# SCH_My-USB-Hub_2024-06-27.net
KiCad netlist of a schematic drawn in EasyEDA
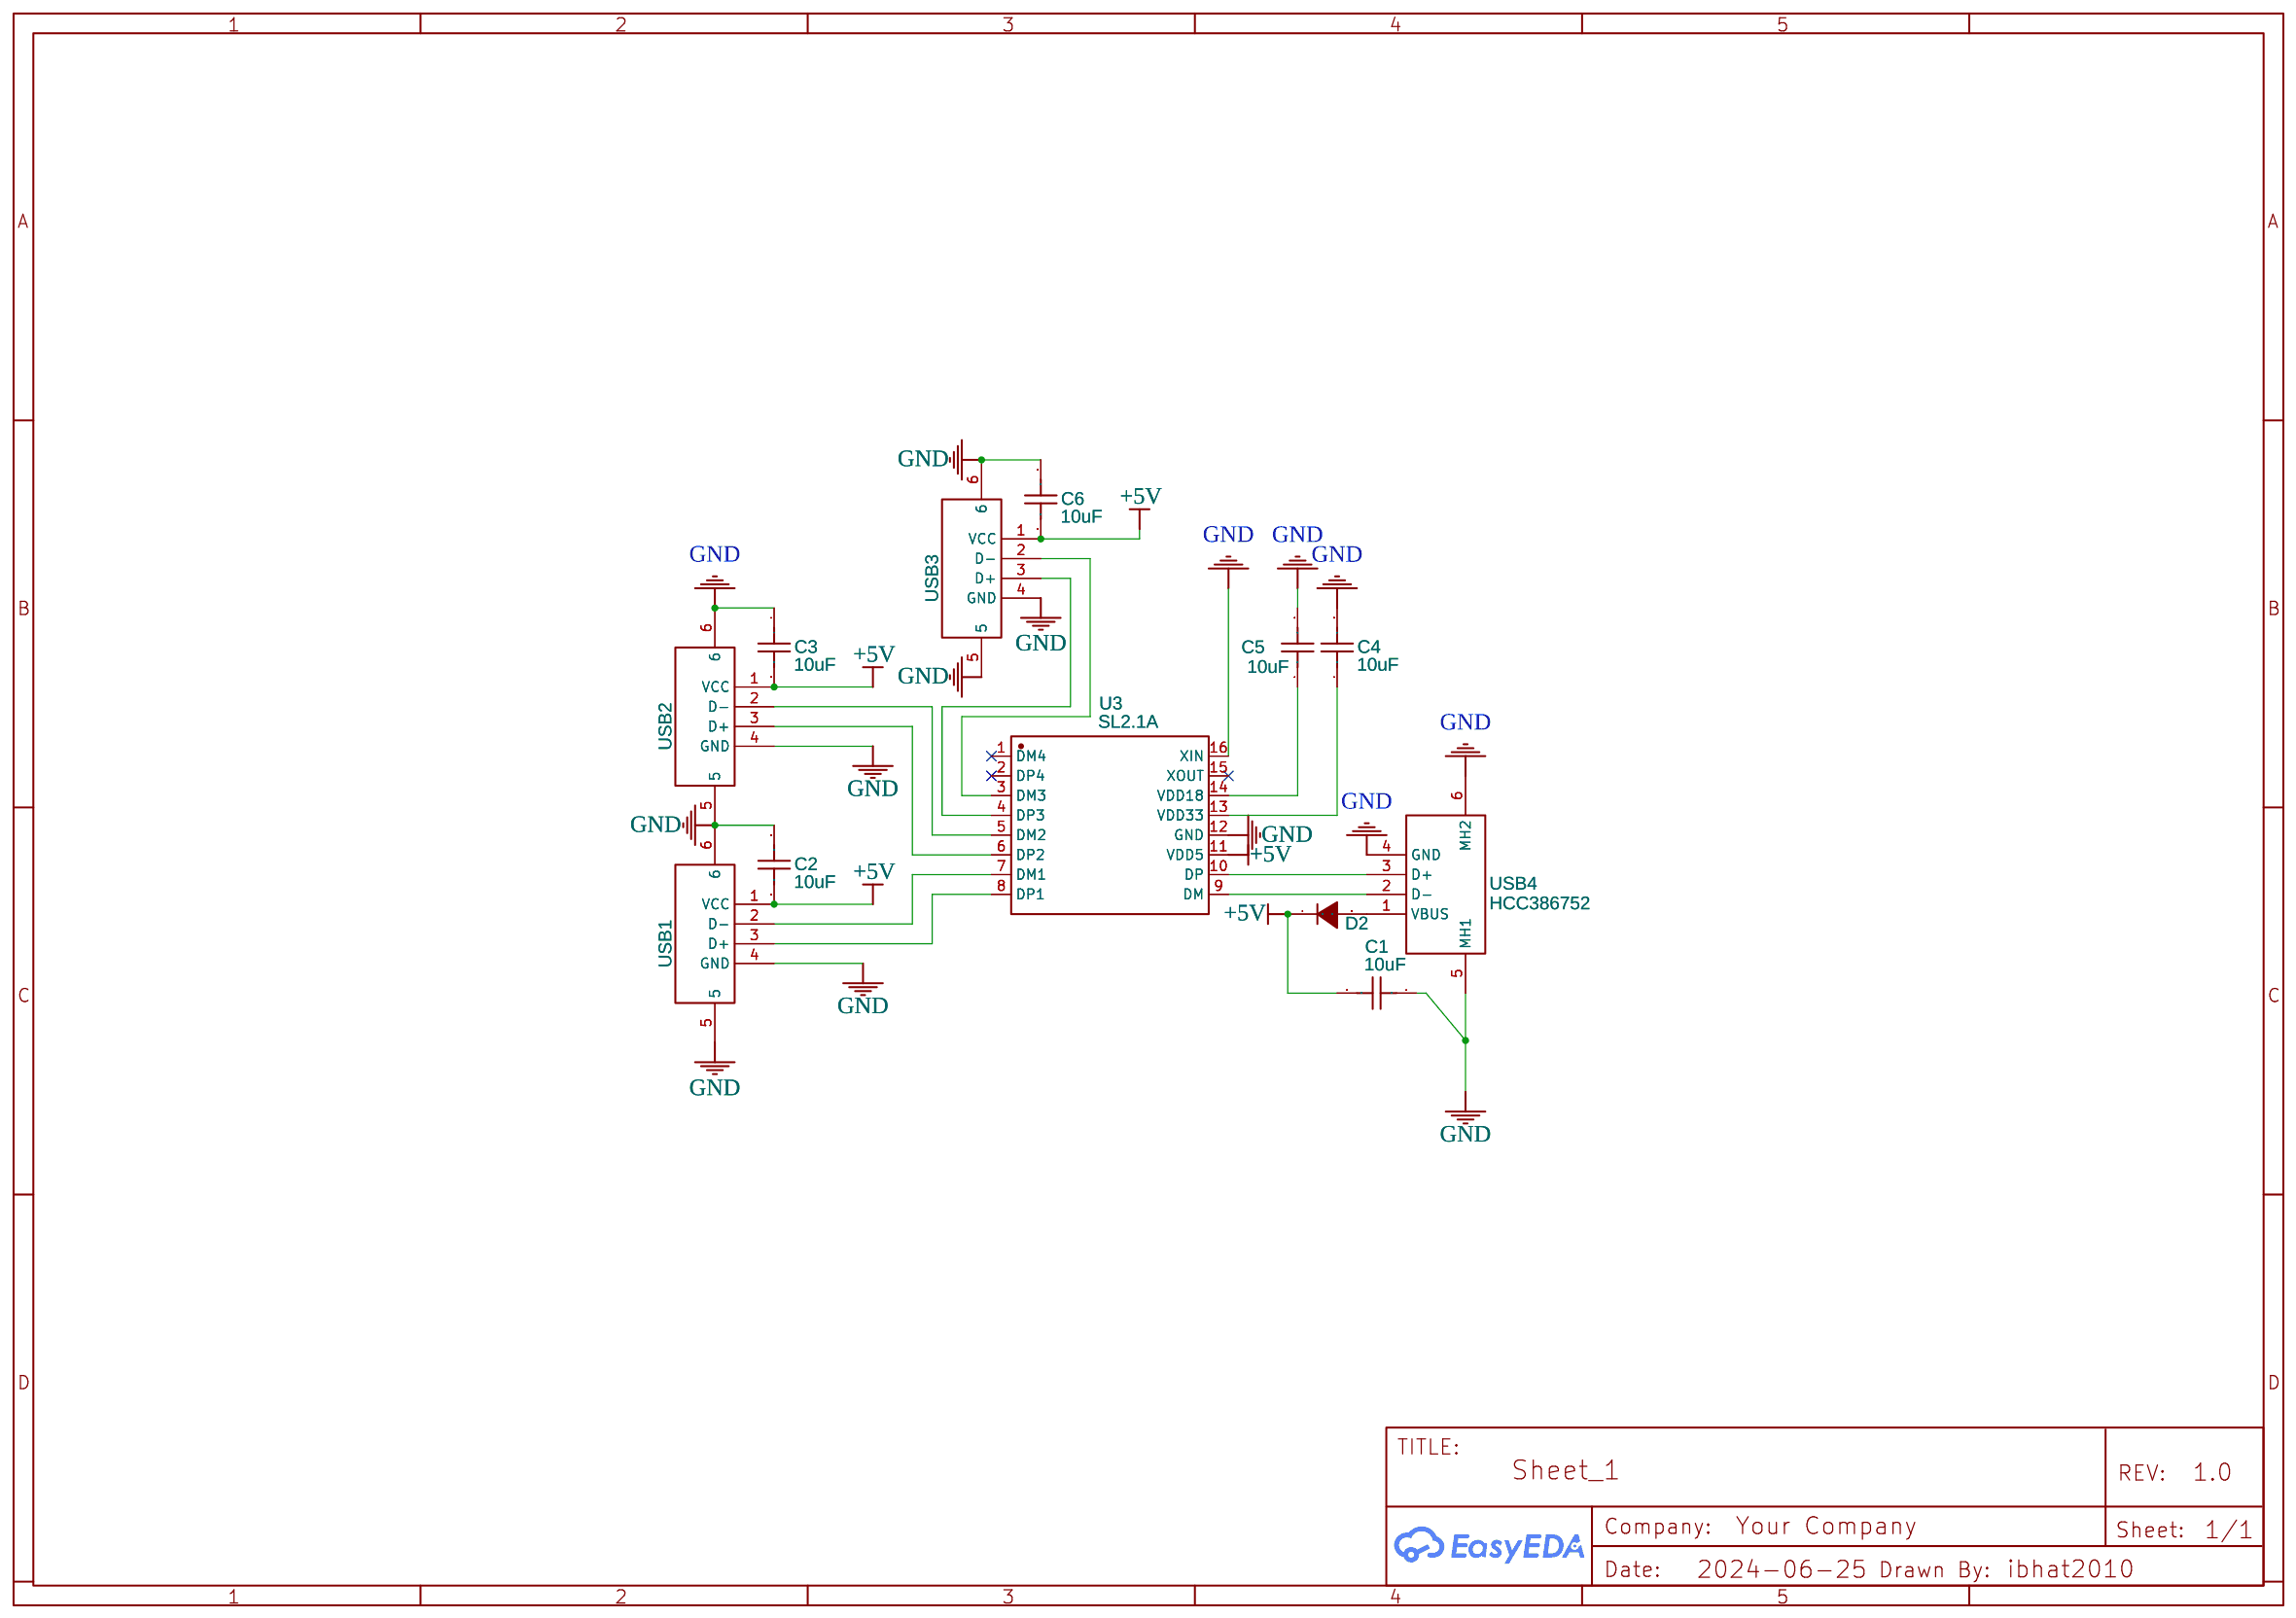
[diagram p0: schematic sheet]

(export (version "E")
  (design (tool "Eeschema 10.0.6"))
  (components
    (comp (ref "C1")
      (value "10uF")
      (fields
        (field (name "Manufacturer Part") "CL10A106KP8NNNC")
        (field (name "Manufacturer") "SAMSUNG(三星)")
      )
      (libsource (lib "") (part "CL10A106KP8NNNC_1"))
    )
    (comp (ref "C2")
      (value "10uF")
      (fields
        (field (name "Manufacturer Part") "CL10A106KP8NNNC")
        (field (name "Manufacturer") "SAMSUNG(三星)")
      )
      (libsource (lib "") (part "CL10A106KP8NNNC"))
    )
    (comp (ref "C3")
      (value "10uF")
      (fields
        (field (name "Manufacturer Part") "CL10A106KP8NNNC")
        (field (name "Manufacturer") "SAMSUNG(三星)")
      )
      (libsource (lib "") (part "CL10A106KP8NNNC"))
    )
    (comp (ref "C4") (value "10uF") (libsource (lib "") (part "C_0603_US")))
    (comp (ref "C5") (value "10uF") (libsource (lib "") (part "C_0603_US")))
    (comp (ref "C6")
      (value "10uF")
      (fields
        (field (name "Manufacturer Part") "CL10A106KP8NNNC")
        (field (name "Manufacturer") "SAMSUNG(三星)")
      )
      (libsource (lib "") (part "CL10A106KP8NNNC"))
    )
    (comp (ref "D2")
      (value "NSR0320MW2T1G")
      (fields (field (name "Manufacturer") "onsemi(安森美)"))
      (libsource (lib "") (part "NSR0320MW2T1G"))
    )
    (comp (ref "U3")
      (value "SL2.1A")
      (fields (field (name "Manufacturer") "CoreChips(和芯润德)"))
      (libsource (lib "") (part "SL2.1A"))
    )
    (comp (ref "USB1")
      (value "USB-AF-90-14.4X13.6-H7.0-DIP")
      (fields (field (name "Manufacturer Part") "903-131A1011D10100") (field (name "Manufacturer") "精拓金"))
      (libsource (lib "") (part "USB-AF-90-14.4X13.6-H7.0-DIP"))
    )
    (comp (ref "USB2")
      (value "USB-AF-90-14.4X13.6-H7.0-DIP")
      (fields (field (name "Manufacturer Part") "903-131A1011D10100") (field (name "Manufacturer") "精拓金"))
      (libsource (lib "") (part "USB-AF-90-14.4X13.6-H7.0-DIP"))
    )
    (comp (ref "USB3")
      (value "USB-AF-90-14.4X13.6-H7.0-DIP")
      (fields (field (name "Manufacturer Part") "903-131A1011D10100") (field (name "Manufacturer") "精拓金"))
      (libsource (lib "") (part "USB-AF-90-14.4X13.6-H7.0-DIP"))
    )
    (comp (ref "USB4")
      (value "HCC386752")
      (fields (field (name "Manufacturer Part") "U-USBAR04P-M003") (field (name "Manufacturer") "Ckmtw(灿科盟)"))
      (libsource (lib "") (part "HCC386752"))
    )
  )
  (nets
    (net (code "1") (name "+5V") (class "Default")
      (node (ref "C1") (pin "2") (pinfunction "2_2") (pintype "unspecified"))
      (node (ref "C2") (pin "2") (pinfunction "2_2") (pintype "unspecified"))
      (node (ref "C3") (pin "2") (pinfunction "2_2") (pintype "unspecified"))
      (node (ref "C6") (pin "2") (pinfunction "2_2") (pintype "unspecified"))
      (node (ref "D2") (pin "1") (pinfunction "C_1") (pintype "unspecified"))
      (node (ref "U3") (pin "11") (pinfunction "VDD5_11") (pintype "unspecified"))
      (node (ref "USB1") (pin "1") (pinfunction "VCC_1") (pintype "unspecified"))
      (node (ref "USB2") (pin "1") (pinfunction "VCC_1") (pintype "unspecified"))
      (node (ref "USB3") (pin "1") (pinfunction "VCC_1") (pintype "unspecified"))
    )
    (net (code "2") (name "GND") (class "Default")
      (node (ref "C1") (pin "1") (pinfunction "1_1") (pintype "unspecified"))
      (node (ref "C2") (pin "1") (pinfunction "1_1") (pintype "unspecified"))
      (node (ref "C3") (pin "1") (pinfunction "1_1") (pintype "unspecified"))
      (node (ref "C4") (pin "2") (pinfunction "2_2") (pintype "unspecified"))
      (node (ref "C5") (pin "2") (pinfunction "2_2") (pintype "unspecified"))
      (node (ref "C6") (pin "1") (pinfunction "1_1") (pintype "unspecified"))
      (node (ref "U3") (pin "12") (pinfunction "GND_12") (pintype "unspecified"))
      (node (ref "U3") (pin "16") (pinfunction "XIN_16") (pintype "unspecified"))
      (node (ref "USB1") (pin "4") (pinfunction "GND_4") (pintype "unspecified"))
      (node (ref "USB1") (pin "5") (pinfunction "5_5") (pintype "unspecified"))
      (node (ref "USB1") (pin "6") (pinfunction "6_6") (pintype "unspecified"))
      (node (ref "USB2") (pin "4") (pinfunction "GND_4") (pintype "unspecified"))
      (node (ref "USB2") (pin "5") (pinfunction "5_5") (pintype "unspecified"))
      (node (ref "USB2") (pin "6") (pinfunction "6_6") (pintype "unspecified"))
      (node (ref "USB3") (pin "4") (pinfunction "GND_4") (pintype "unspecified"))
      (node (ref "USB3") (pin "5") (pinfunction "5_5") (pintype "unspecified"))
      (node (ref "USB3") (pin "6") (pinfunction "6_6") (pintype "unspecified"))
      (node (ref "USB4") (pin "4") (pinfunction "GND_4") (pintype "unspecified"))
      (node (ref "USB4") (pin "5") (pinfunction "MH1_5") (pintype "unspecified"))
      (node (ref "USB4") (pin "6") (pinfunction "MH2_6") (pintype "unspecified"))
    )
    (net (code "3") (name "Net-(D2-A)") (class "Default")
      (node (ref "D2") (pin "2") (pinfunction "A_2") (pintype "unspecified"))
      (node (ref "USB4") (pin "1") (pinfunction "VBUS_1") (pintype "unspecified"))
    )
    (net (code "4") (name "Net-(U3-DM)") (class "Default")
      (node (ref "U3") (pin "9") (pinfunction "DM_9") (pintype "unspecified"))
      (node (ref "USB4") (pin "2") (pinfunction "D-_2") (pintype "unspecified"))
    )
    (net (code "5") (name "Net-(U3-DM1)") (class "Default")
      (node (ref "U3") (pin "7") (pinfunction "DM1_7") (pintype "unspecified"))
      (node (ref "USB1") (pin "2") (pinfunction "D-_2") (pintype "unspecified"))
    )
    (net (code "6") (name "Net-(U3-DM2)") (class "Default")
      (node (ref "U3") (pin "5") (pinfunction "DM2_5") (pintype "unspecified"))
      (node (ref "USB2") (pin "2") (pinfunction "D-_2") (pintype "unspecified"))
    )
    (net (code "7") (name "Net-(U3-DM3)") (class "Default")
      (node (ref "U3") (pin "3") (pinfunction "DM3_3") (pintype "unspecified"))
      (node (ref "USB3") (pin "2") (pinfunction "D-_2") (pintype "unspecified"))
    )
    (net (code "8") (name "Net-(U3-DP)") (class "Default")
      (node (ref "U3") (pin "10") (pinfunction "DP_10") (pintype "unspecified"))
      (node (ref "USB4") (pin "3") (pinfunction "D+_3") (pintype "unspecified"))
    )
    (net (code "9") (name "Net-(U3-DP1)") (class "Default")
      (node (ref "U3") (pin "8") (pinfunction "DP1_8") (pintype "unspecified"))
      (node (ref "USB1") (pin "3") (pinfunction "D+_3") (pintype "unspecified"))
    )
    (net (code "10") (name "Net-(U3-DP2)") (class "Default")
      (node (ref "U3") (pin "6") (pinfunction "DP2_6") (pintype "unspecified"))
      (node (ref "USB2") (pin "3") (pinfunction "D+_3") (pintype "unspecified"))
    )
    (net (code "11") (name "Net-(U3-DP3)") (class "Default")
      (node (ref "U3") (pin "4") (pinfunction "DP3_4") (pintype "unspecified"))
      (node (ref "USB3") (pin "3") (pinfunction "D+_3") (pintype "unspecified"))
    )
    (net (code "12") (name "Net-(U3-VDD18)") (class "Default")
      (node (ref "C5") (pin "1") (pinfunction "1_1") (pintype "unspecified"))
      (node (ref "U3") (pin "14") (pinfunction "VDD18_14") (pintype "unspecified"))
    )
    (net (code "13") (name "Net-(U3-VDD33)") (class "Default")
      (node (ref "C4") (pin "1") (pinfunction "1_1") (pintype "unspecified"))
      (node (ref "U3") (pin "13") (pinfunction "VDD33_13") (pintype "unspecified"))
    )
    (net (code "14") (name "unconnected-(U3-DM4-Pad1)") (class "Default")
      (node (ref "U3") (pin "1") (pinfunction "DM4_1") (pintype "unspecified+no_connect"))
    )
    (net (code "15") (name "unconnected-(U3-DP4-Pad2)") (class "Default")
      (node (ref "U3") (pin "2") (pinfunction "DP4_2") (pintype "unspecified+no_connect"))
    )
    (net (code "16") (name "unconnected-(U3-XOUT-Pad15)") (class "Default")
      (node (ref "U3") (pin "15") (pinfunction "XOUT_15") (pintype "unspecified+no_connect"))
    )
  )
)
